# parport.net
KiCad netlist of a schematic drawn in EAGLE
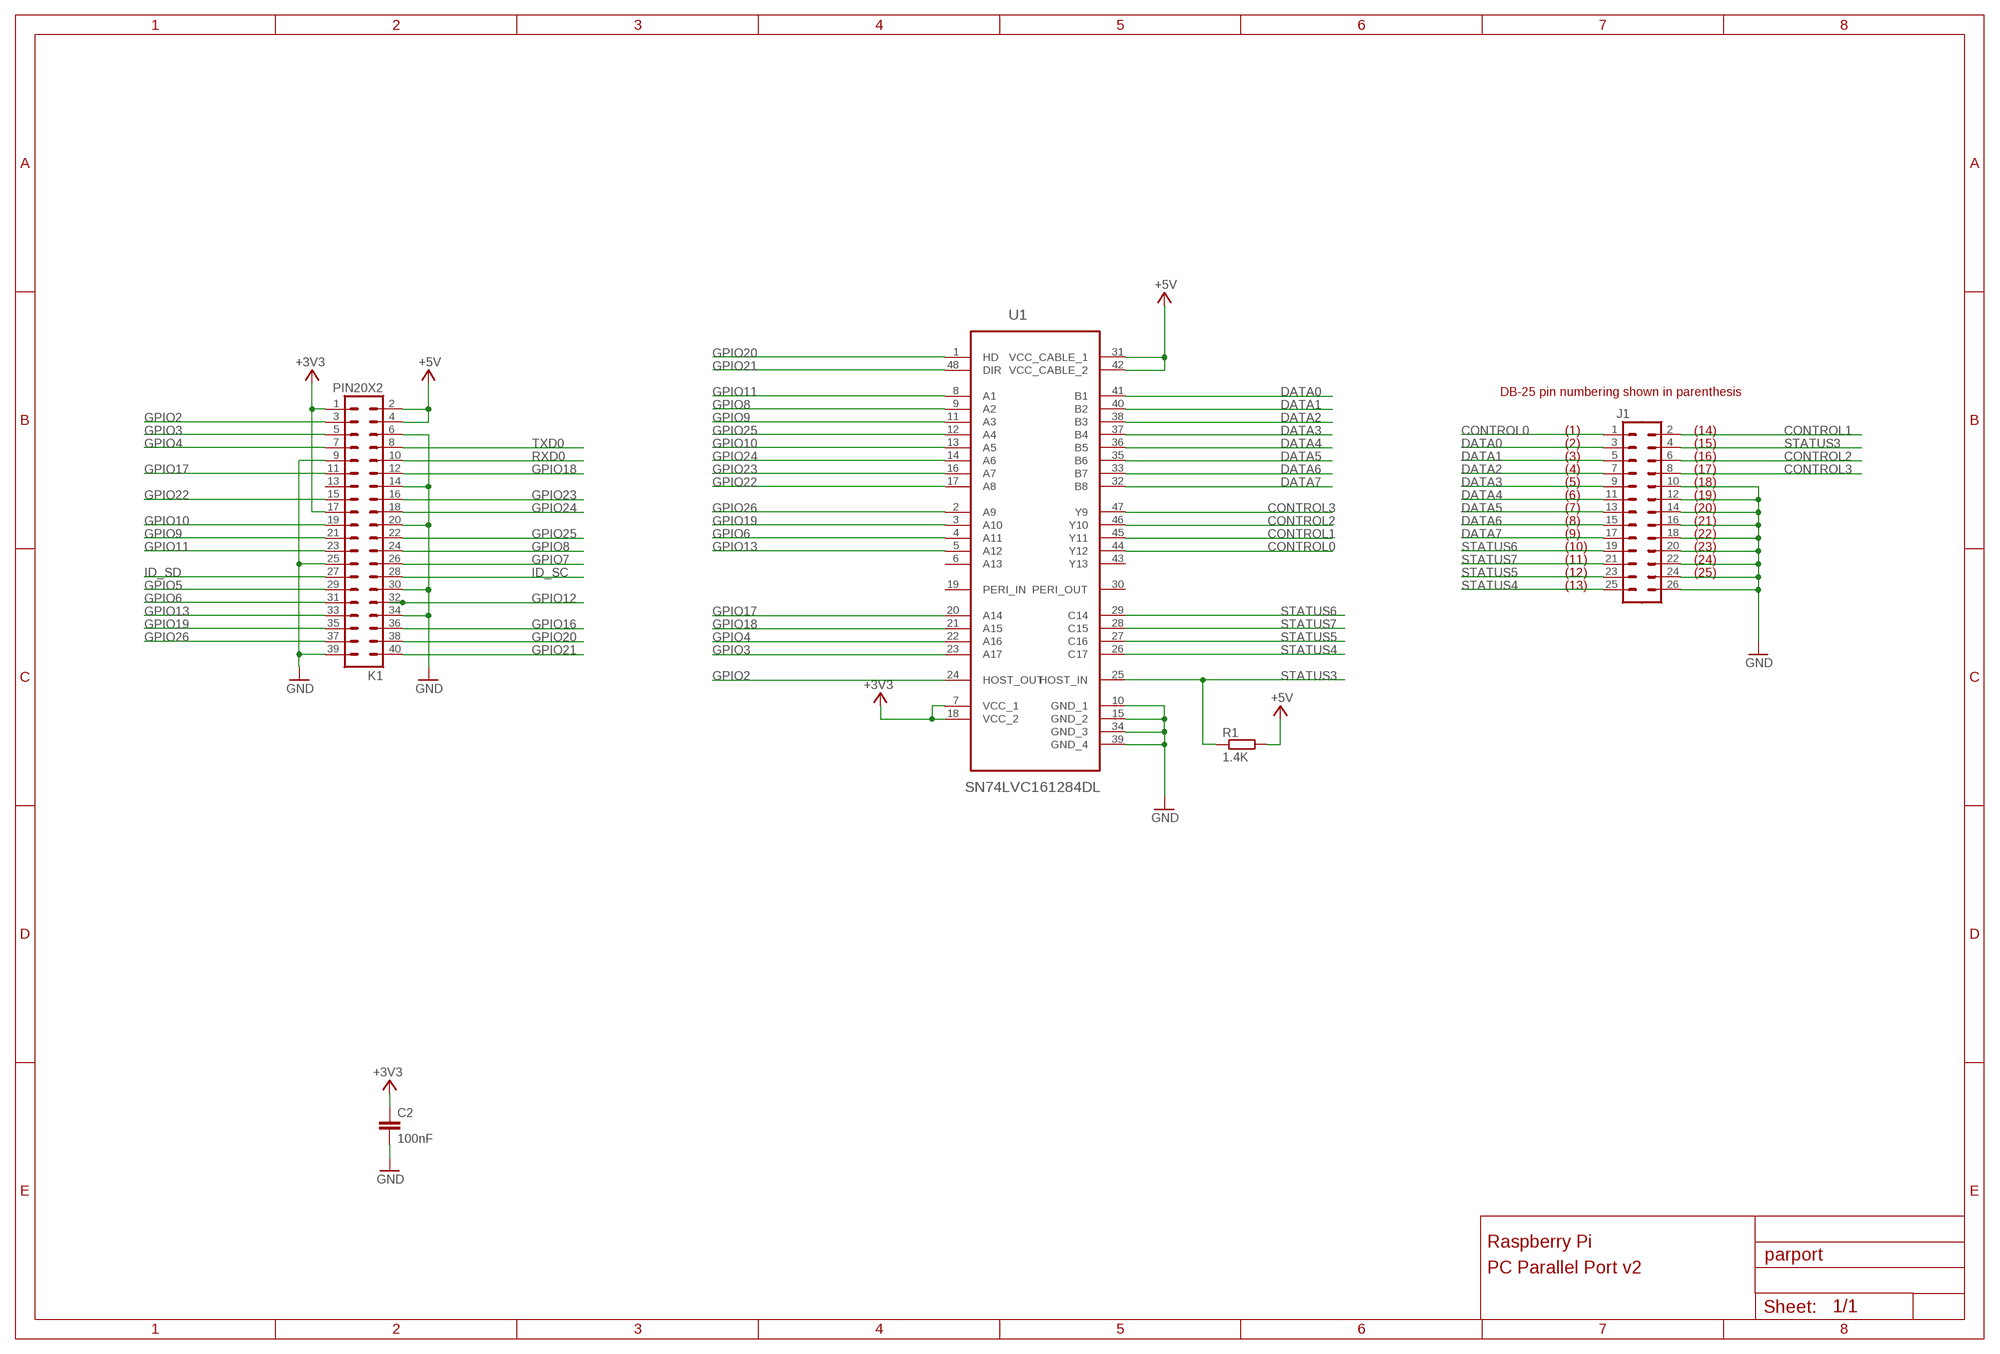
[diagram p0: schematic, sheet 1]

(export (version "E")
  (design (tool "Eeschema 10.0.6"))
  (components
    (comp (ref "C2")
      (value "100nF")
      (footprint "eagle-import:C0805")
      (libsource (lib "eagle-import") (part "C-EUC0805"))
    )
    (comp (ref "J1")
      (value "M13X22X13")
      (footprint "eagle-import:2X13")
      (libsource (lib "eagle-import") (part "M13X22X13"))
    )
    (comp (ref "K1")
      (value "PIN20X2")
      (footprint "eagle-import:PIN_20X2")
      (libsource (lib "eagle-import") (part "PIN20X2"))
    )
    (comp (ref "R1")
      (value "1.4K")
      (footprint "eagle-import:R0805")
      (libsource (lib "eagle-import") (part "R-EU_R0805"))
    )
    (comp (ref "U1")
      (value "SN74LVC161284DL")
      (footprint "eagle-import:SOP63P1035X279-48N")
      (libsource (lib "eagle-import") (part "SN74LVC161284DL"))
    )
  )
  (nets
    (net (code "1") (name "+3V3") (class "Default")
      (node (ref "C2") (pin "1") (pinfunction "1_1") (pintype "passive"))
      (node (ref "K1") (pin "1") (pinfunction "1_1") (pintype "passive"))
      (node (ref "K1") (pin "17") (pinfunction "17_17") (pintype "passive"))
      (node (ref "U1") (pin "18") (pinfunction "VCC_2_18") (pintype "input"))
      (node (ref "U1") (pin "7") (pinfunction "VCC_1_7") (pintype "input"))
    )
    (net (code "2") (name "+5V") (class "Default")
      (node (ref "K1") (pin "2") (pinfunction "2_2") (pintype "passive"))
      (node (ref "K1") (pin "4") (pinfunction "4_4") (pintype "passive"))
      (node (ref "R1") (pin "2") (pinfunction "2_2") (pintype "passive"))
      (node (ref "U1") (pin "31") (pinfunction "VCC_CABLE_1_31") (pintype "passive"))
      (node (ref "U1") (pin "42") (pinfunction "VCC_CABLE_2_42") (pintype "output"))
    )
    (net (code "3") (name "/CONTROL0") (class "Default")
      (node (ref "J1") (pin "1") (pinfunction "1_1") (pintype "passive"))
      (node (ref "U1") (pin "44") (pinfunction "Y12_44") (pintype "output"))
    )
    (net (code "4") (name "/CONTROL1") (class "Default")
      (node (ref "J1") (pin "2") (pinfunction "2_2") (pintype "passive"))
      (node (ref "U1") (pin "45") (pinfunction "Y11_45") (pintype "output"))
    )
    (net (code "5") (name "/CONTROL2") (class "Default")
      (node (ref "J1") (pin "6") (pinfunction "6_6") (pintype "passive"))
      (node (ref "U1") (pin "46") (pinfunction "Y10_46") (pintype "output"))
    )
    (net (code "6") (name "/CONTROL3") (class "Default")
      (node (ref "J1") (pin "8") (pinfunction "8_8") (pintype "passive"))
      (node (ref "U1") (pin "47") (pinfunction "Y9_47") (pintype "output"))
    )
    (net (code "7") (name "/DATA0") (class "Default")
      (node (ref "J1") (pin "3") (pinfunction "3_3") (pintype "passive"))
      (node (ref "U1") (pin "41") (pinfunction "B1_41") (pintype "output"))
    )
    (net (code "8") (name "/DATA1") (class "Default")
      (node (ref "J1") (pin "5") (pinfunction "5_5") (pintype "passive"))
      (node (ref "U1") (pin "40") (pinfunction "B2_40") (pintype "output"))
    )
    (net (code "9") (name "/DATA2") (class "Default")
      (node (ref "J1") (pin "7") (pinfunction "7_7") (pintype "passive"))
      (node (ref "U1") (pin "38") (pinfunction "B3_38") (pintype "output"))
    )
    (net (code "10") (name "/DATA3") (class "Default")
      (node (ref "J1") (pin "9") (pinfunction "9_9") (pintype "passive"))
      (node (ref "U1") (pin "37") (pinfunction "B4_37") (pintype "output"))
    )
    (net (code "11") (name "/DATA4") (class "Default")
      (node (ref "J1") (pin "11") (pinfunction "11_11") (pintype "passive"))
      (node (ref "U1") (pin "36") (pinfunction "B5_36") (pintype "output"))
    )
    (net (code "12") (name "/DATA5") (class "Default")
      (node (ref "J1") (pin "13") (pinfunction "13_13") (pintype "passive"))
      (node (ref "U1") (pin "35") (pinfunction "B6_35") (pintype "output"))
    )
    (net (code "13") (name "/DATA6") (class "Default")
      (node (ref "J1") (pin "15") (pinfunction "15_15") (pintype "passive"))
      (node (ref "U1") (pin "33") (pinfunction "B7_33") (pintype "output"))
    )
    (net (code "14") (name "/DATA7") (class "Default")
      (node (ref "J1") (pin "17") (pinfunction "17_17") (pintype "passive"))
      (node (ref "U1") (pin "32") (pinfunction "B8_32") (pintype "passive"))
    )
    (net (code "15") (name "/GPIO2") (class "Default")
      (node (ref "K1") (pin "3") (pinfunction "3_3") (pintype "passive"))
      (node (ref "U1") (pin "24") (pinfunction "HOST_OUT_24") (pintype "input"))
    )
    (net (code "16") (name "/GPIO3") (class "Default")
      (node (ref "K1") (pin "5") (pinfunction "5_5") (pintype "passive"))
      (node (ref "U1") (pin "23") (pinfunction "A17_23") (pintype "input"))
    )
    (net (code "17") (name "/GPIO4") (class "Default")
      (node (ref "K1") (pin "7") (pinfunction "7_7") (pintype "passive"))
      (node (ref "U1") (pin "22") (pinfunction "A16_22") (pintype "input"))
    )
    (net (code "18") (name "/GPIO5") (class "Default")
      (node (ref "K1") (pin "29") (pinfunction "29_29") (pintype "passive"))
    )
    (net (code "19") (name "/GPIO6") (class "Default")
      (node (ref "K1") (pin "31") (pinfunction "31_31") (pintype "passive"))
      (node (ref "U1") (pin "4") (pinfunction "A11_4") (pintype "power_in"))
    )
    (net (code "20") (name "/GPIO7") (class "Default")
      (node (ref "K1") (pin "26") (pinfunction "26_26") (pintype "passive"))
    )
    (net (code "21") (name "/GPIO8") (class "Default")
      (node (ref "K1") (pin "24") (pinfunction "24_24") (pintype "passive"))
      (node (ref "U1") (pin "9") (pinfunction "A2_9") (pintype "input"))
    )
    (net (code "22") (name "/GPIO9") (class "Default")
      (node (ref "K1") (pin "21") (pinfunction "21_21") (pintype "passive"))
      (node (ref "U1") (pin "11") (pinfunction "A3_11") (pintype "input"))
    )
    (net (code "23") (name "/GPIO10") (class "Default")
      (node (ref "K1") (pin "19") (pinfunction "19_19") (pintype "passive"))
      (node (ref "U1") (pin "13") (pinfunction "A5_13") (pintype "input"))
    )
    (net (code "24") (name "/GPIO11") (class "Default")
      (node (ref "K1") (pin "23") (pinfunction "23_23") (pintype "passive"))
      (node (ref "U1") (pin "8") (pinfunction "A1_8") (pintype "input"))
    )
    (net (code "25") (name "/GPIO12") (class "Default")
      (node (ref "K1") (pin "32") (pinfunction "32_32") (pintype "passive"))
    )
    (net (code "26") (name "/GPIO13") (class "Default")
      (node (ref "K1") (pin "33") (pinfunction "33_33") (pintype "passive"))
      (node (ref "U1") (pin "5") (pinfunction "A12_5") (pintype "input"))
    )
    (net (code "27") (name "/GPIO16") (class "Default")
      (node (ref "K1") (pin "36") (pinfunction "36_36") (pintype "passive"))
    )
    (net (code "28") (name "/GPIO17") (class "Default")
      (node (ref "K1") (pin "11") (pinfunction "11_11") (pintype "passive"))
      (node (ref "U1") (pin "20") (pinfunction "A14_20") (pintype "input"))
    )
    (net (code "29") (name "/GPIO18") (class "Default")
      (node (ref "K1") (pin "12") (pinfunction "12_12") (pintype "passive"))
      (node (ref "U1") (pin "21") (pinfunction "A15_21") (pintype "input"))
    )
    (net (code "30") (name "/GPIO19") (class "Default")
      (node (ref "K1") (pin "35") (pinfunction "35_35") (pintype "passive"))
      (node (ref "U1") (pin "3") (pinfunction "A10_3") (pintype "power_in"))
    )
    (net (code "31") (name "/GPIO20") (class "Default")
      (node (ref "K1") (pin "38") (pinfunction "38_38") (pintype "passive"))
      (node (ref "U1") (pin "1") (pinfunction "HD_1") (pintype "power_in"))
    )
    (net (code "32") (name "/GPIO21") (class "Default")
      (node (ref "K1") (pin "40") (pinfunction "40_40") (pintype "passive"))
      (node (ref "U1") (pin "48") (pinfunction "DIR_48") (pintype "output"))
    )
    (net (code "33") (name "/GPIO22") (class "Default")
      (node (ref "K1") (pin "15") (pinfunction "15_15") (pintype "passive"))
      (node (ref "U1") (pin "17") (pinfunction "A8_17") (pintype "input"))
    )
    (net (code "34") (name "/GPIO23") (class "Default")
      (node (ref "K1") (pin "16") (pinfunction "16_16") (pintype "passive"))
      (node (ref "U1") (pin "16") (pinfunction "A7_16") (pintype "input"))
    )
    (net (code "35") (name "/GPIO24") (class "Default")
      (node (ref "K1") (pin "18") (pinfunction "18_18") (pintype "passive"))
      (node (ref "U1") (pin "14") (pinfunction "A6_14") (pintype "input"))
    )
    (net (code "36") (name "/GPIO25") (class "Default")
      (node (ref "K1") (pin "22") (pinfunction "22_22") (pintype "passive"))
      (node (ref "U1") (pin "12") (pinfunction "A4_12") (pintype "input"))
    )
    (net (code "37") (name "/GPIO26") (class "Default")
      (node (ref "K1") (pin "37") (pinfunction "37_37") (pintype "passive"))
      (node (ref "U1") (pin "2") (pinfunction "A9_2") (pintype "power_in"))
    )
    (net (code "38") (name "/ID_SC") (class "Default")
      (node (ref "K1") (pin "28") (pinfunction "28_28") (pintype "passive"))
    )
    (net (code "39") (name "/ID_SD") (class "Default")
      (node (ref "K1") (pin "27") (pinfunction "27_27") (pintype "passive"))
    )
    (net (code "40") (name "/RXD0") (class "Default")
      (node (ref "K1") (pin "10") (pinfunction "10_10") (pintype "passive"))
    )
    (net (code "41") (name "/STATUS3") (class "Default")
      (node (ref "J1") (pin "4") (pinfunction "4_4") (pintype "passive"))
      (node (ref "R1") (pin "1") (pinfunction "1_1") (pintype "passive"))
      (node (ref "U1") (pin "25") (pinfunction "HOST_IN_25") (pintype "passive"))
    )
    (net (code "42") (name "/STATUS4") (class "Default")
      (node (ref "J1") (pin "25") (pinfunction "25_25") (pintype "passive"))
      (node (ref "U1") (pin "26") (pinfunction "C17_26") (pintype "passive"))
    )
    (net (code "43") (name "/STATUS5") (class "Default")
      (node (ref "J1") (pin "23") (pinfunction "23_23") (pintype "passive"))
      (node (ref "U1") (pin "27") (pinfunction "C16_27") (pintype "passive"))
    )
    (net (code "44") (name "/STATUS6") (class "Default")
      (node (ref "J1") (pin "19") (pinfunction "19_19") (pintype "passive"))
      (node (ref "U1") (pin "29") (pinfunction "C14_29") (pintype "passive"))
    )
    (net (code "45") (name "/STATUS7") (class "Default")
      (node (ref "J1") (pin "21") (pinfunction "21_21") (pintype "passive"))
      (node (ref "U1") (pin "28") (pinfunction "C15_28") (pintype "passive"))
    )
    (net (code "46") (name "/TXD0") (class "Default")
      (node (ref "K1") (pin "8") (pinfunction "8_8") (pintype "passive"))
    )
    (net (code "47") (name "GND") (class "Default")
      (node (ref "C2") (pin "2") (pinfunction "2_2") (pintype "passive"))
      (node (ref "J1") (pin "10") (pinfunction "10_10") (pintype "passive"))
      (node (ref "J1") (pin "12") (pinfunction "12_12") (pintype "passive"))
      (node (ref "J1") (pin "14") (pinfunction "14_14") (pintype "passive"))
      (node (ref "J1") (pin "16") (pinfunction "16_16") (pintype "passive"))
      (node (ref "J1") (pin "18") (pinfunction "18_18") (pintype "passive"))
      (node (ref "J1") (pin "20") (pinfunction "20_20") (pintype "passive"))
      (node (ref "J1") (pin "22") (pinfunction "22_22") (pintype "passive"))
      (node (ref "J1") (pin "24") (pinfunction "24_24") (pintype "passive"))
      (node (ref "J1") (pin "26") (pinfunction "26_26") (pintype "passive"))
      (node (ref "K1") (pin "14") (pinfunction "14_14") (pintype "passive"))
      (node (ref "K1") (pin "20") (pinfunction "20_20") (pintype "passive"))
      (node (ref "K1") (pin "25") (pinfunction "25_25") (pintype "passive"))
      (node (ref "K1") (pin "30") (pinfunction "30_30") (pintype "passive"))
      (node (ref "K1") (pin "34") (pinfunction "34_34") (pintype "passive"))
      (node (ref "K1") (pin "39") (pinfunction "39_39") (pintype "passive"))
      (node (ref "K1") (pin "6") (pinfunction "6_6") (pintype "passive"))
      (node (ref "K1") (pin "9") (pinfunction "9_9") (pintype "passive"))
      (node (ref "U1") (pin "10") (pinfunction "GND_1_10") (pintype "input"))
      (node (ref "U1") (pin "15") (pinfunction "GND_2_15") (pintype "input"))
      (node (ref "U1") (pin "34") (pinfunction "GND_3_34") (pintype "output"))
      (node (ref "U1") (pin "39") (pinfunction "GND_4_39") (pintype "output"))
    )
    (net (code "48") (name "unconnected-(K1-Pad13)") (class "Default")
      (node (ref "K1") (pin "13") (pinfunction "13_13") (pintype "passive"))
    )
    (net (code "49") (name "unconnected-(U1-A13-Pad6)") (class "Default")
      (node (ref "U1") (pin "6") (pinfunction "A13_6") (pintype "input"))
    )
    (net (code "50") (name "unconnected-(U1-PERI_IN-Pad19)") (class "Default")
      (node (ref "U1") (pin "19") (pinfunction "PERI_IN_19") (pintype "input"))
    )
    (net (code "51") (name "unconnected-(U1-PERI_OUT-Pad30)") (class "Default")
      (node (ref "U1") (pin "30") (pinfunction "PERI_OUT_30") (pintype "passive"))
    )
    (net (code "52") (name "unconnected-(U1-Y13-Pad43)") (class "Default")
      (node (ref "U1") (pin "43") (pinfunction "Y13_43") (pintype "output"))
    )
  )
)
